# SiliconMind.net
KiCad netlist of a schematic drawn in EAGLE
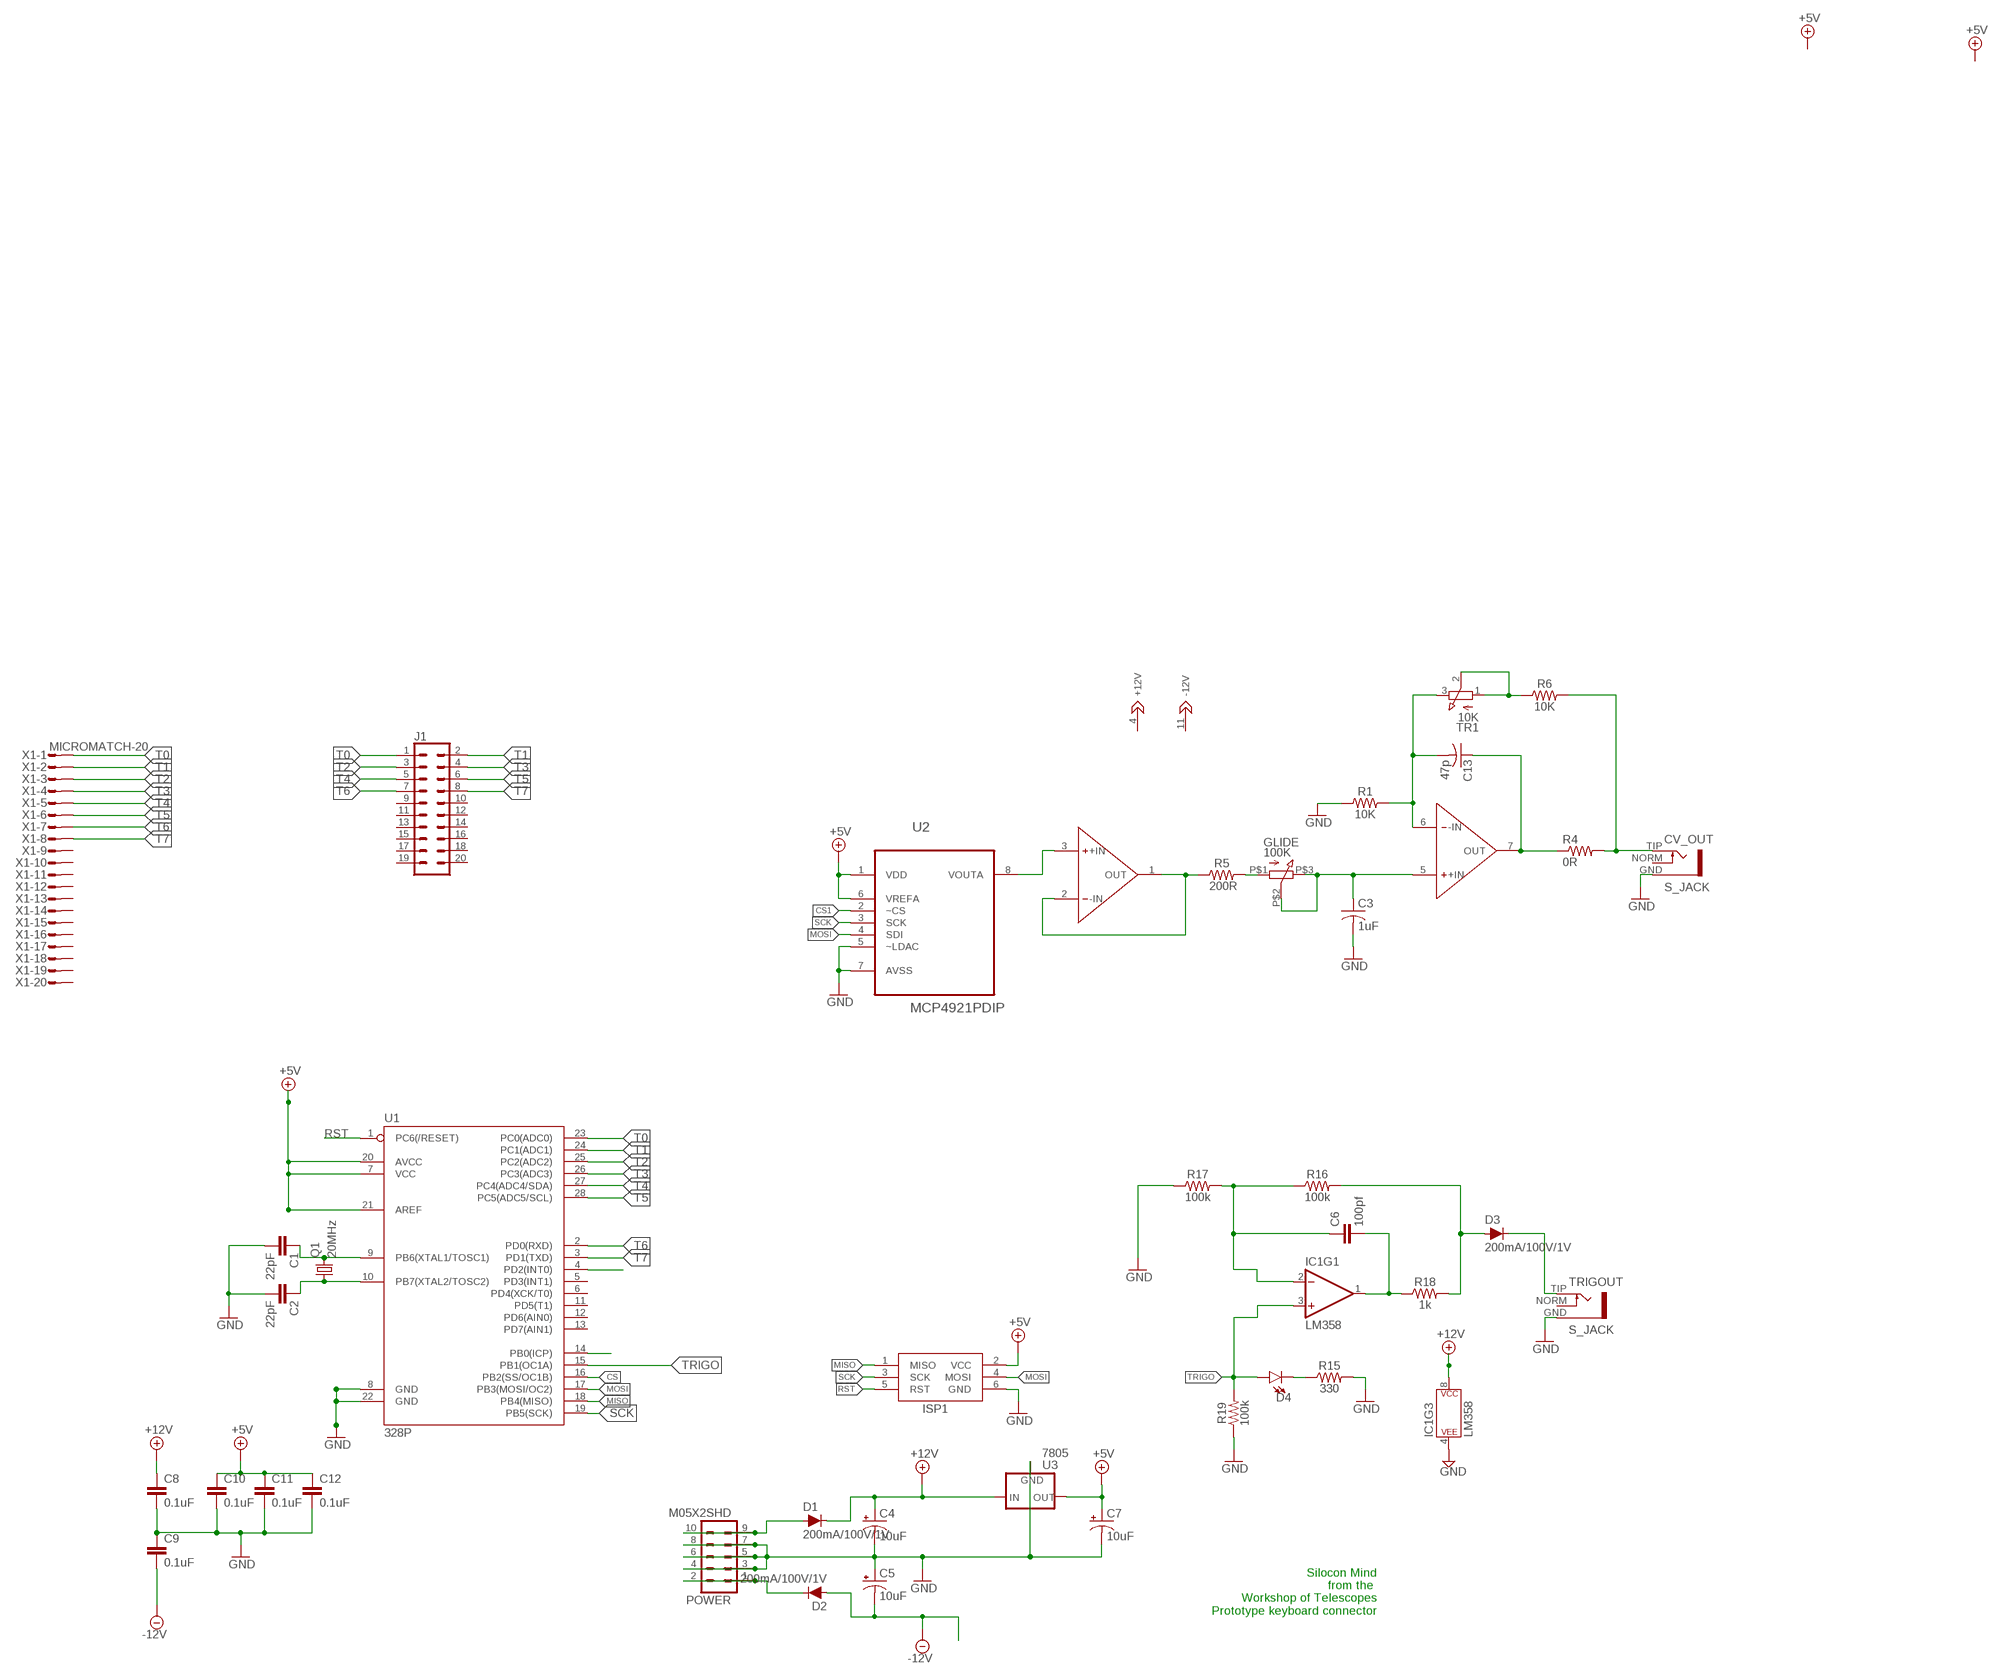
[diagram p0: schematic, sheet 1]

(export (version "E")
  (design (tool "Eeschema 10.0.6"))
  (components
    (comp (ref "C1")
      (value "22pF")
      (footprint "eagle-import:CAP-PTH-2.54")
      (libsource (lib "eagle-import") (part "22PF-PTH-2.54MM-200V-5%"))
    )
    (comp (ref "C2")
      (value "22pF")
      (footprint "eagle-import:CAP-PTH-2.54")
      (libsource (lib "eagle-import") (part "22PF-PTH-2.54MM-200V-5%"))
    )
    (comp (ref "C3")
      (value "1uF")
      (footprint "eagle-import:C0805K")
      (libsource (lib "eagle-import") (part "C-USC0805K"))
    )
    (comp (ref "C4")
      (value "10uF")
      (footprint "eagle-import:CPOL-RADIAL-2.5MM-5MM")
      (libsource (lib "eagle-import") (part "10UF-POLAR-RADIAL-2.5MM-25V-20%"))
    )
    (comp (ref "C5")
      (value "10uF")
      (footprint "eagle-import:CPOL-RADIAL-2.5MM-5MM")
      (libsource (lib "eagle-import") (part "10UF-POLAR-RADIAL-2.5MM-25V-20%"))
    )
    (comp (ref "C6")
      (value "100pf")
      (footprint "eagle-import:C075-032X103")
      (libsource (lib "eagle-import") (part "C-EU075-032X103"))
    )
    (comp (ref "C7")
      (value "10uF")
      (footprint "eagle-import:CPOL-RADIAL-2.5MM-5MM")
      (libsource (lib "eagle-import") (part "10UF-POLAR-RADIAL-2.5MM-25V-20%"))
    )
    (comp (ref "C8")
      (value "0.1uF")
      (footprint "eagle-import:CAP-PTH-SMALL-KIT")
      (libsource (lib "eagle-import") (part "0.1UF-KIT-EZ-50V-20%"))
    )
    (comp (ref "C9")
      (value "0.1uF")
      (footprint "eagle-import:CAP-PTH-SMALL-KIT")
      (libsource (lib "eagle-import") (part "0.1UF-KIT-EZ-50V-20%"))
    )
    (comp (ref "C10")
      (value "0.1uF")
      (footprint "eagle-import:CAP-PTH-SMALL-KIT")
      (libsource (lib "eagle-import") (part "0.1UF-KIT-EZ-50V-20%"))
    )
    (comp (ref "C11")
      (value "0.1uF")
      (footprint "eagle-import:CAP-PTH-SMALL-KIT")
      (libsource (lib "eagle-import") (part "0.1UF-KIT-EZ-50V-20%"))
    )
    (comp (ref "C12")
      (value "0.1uF")
      (footprint "eagle-import:CAP-PTH-SMALL-KIT")
      (libsource (lib "eagle-import") (part "0.1UF-KIT-EZ-50V-20%"))
    )
    (comp (ref "C13")
      (value "47p")
      (footprint "eagle-import:C0805K")
      (libsource (lib "eagle-import") (part "C-USC0805K"))
    )
    (comp (ref "CV_OUT")
      (value "S_JACK")
      (footprint "eagle-import:S_JACK")
      (libsource (lib "eagle-import") (part "S_JACK"))
    )
    (comp (ref "D1")
      (value "200mA/100V/1V")
      (footprint "eagle-import:DIODE-1N4148")
      (libsource (lib "eagle-import") (part "DIODE-1N4148"))
    )
    (comp (ref "D2")
      (value "200mA/100V/1V")
      (footprint "eagle-import:DIODE-1N4148")
      (libsource (lib "eagle-import") (part "DIODE-1N4148"))
    )
    (comp (ref "D3")
      (value "200mA/100V/1V")
      (footprint "eagle-import:DIODE-1N4148")
      (libsource (lib "eagle-import") (part "DIODE-1N4148"))
    )
    (comp (ref "D4")
      (value "LED3MM")
      (footprint "eagle-import:LED_3MM")
      (libsource (lib "eagle-import") (part "LED3MM"))
    )
    (comp (ref "GLIDE")
      (value "100K")
      (footprint "eagle-import:Q-POT")
      (libsource (lib "eagle-import") (part "Q-POT"))
    )
    (comp (ref "IC1")
      (value "LM358")
      (footprint "eagle-import:DIP08")
      (libsource (lib "eagle-import") (part "LM358"))
    )
    (comp (ref "ISP1")
      (value "AVRISP-6")
      (footprint "eagle-import:AVRISP")
      (libsource (lib "eagle-import") (part "AVRISP-6"))
    )
    (comp (ref "J1")
      (value "CONN_10X2")
      (footprint "eagle-import:2X10")
      (libsource (lib "eagle-import") (part "CONN_10X2"))
    )
    (comp (ref "POWER")
      (value "M05X2SHD")
      (footprint "eagle-import:2X5-SHROUDED")
      (libsource (lib "eagle-import") (part "M05X2SHD"))
    )
    (comp (ref "Q1")
      (value "20MHz")
      (footprint "eagle-import:HC49U70")
      (libsource (lib "eagle-import") (part "CRYSTALHC49U70"))
    )
    (comp (ref "R1")
      (value "10K")
      (footprint "eagle-import:AXIAL-0.3")
      (libsource (lib "eagle-import") (part "RESISTORAXIAL-0.3"))
    )
    (comp (ref "R4")
      (value "0R")
      (footprint "eagle-import:R0805")
      (libsource (lib "eagle-import") (part "R-US_R0805"))
    )
    (comp (ref "R5")
      (value "200R")
      (footprint "eagle-import:AXIAL-0.3")
      (libsource (lib "eagle-import") (part "RESISTORAXIAL-0.3"))
    )
    (comp (ref "R6")
      (value "10K")
      (footprint "eagle-import:AXIAL-0.3")
      (libsource (lib "eagle-import") (part "RESISTORAXIAL-0.3"))
    )
    (comp (ref "R15")
      (value "330")
      (footprint "eagle-import:AXIAL-0.3")
      (libsource (lib "eagle-import") (part "330OHM-HORIZ-1/10W-5%"))
    )
    (comp (ref "R16")
      (value "100k")
      (footprint "eagle-import:AXIAL-0.3")
      (libsource (lib "eagle-import") (part "100KOHM-HORIZ-1/4W-5%"))
    )
    (comp (ref "R17")
      (value "100k")
      (footprint "eagle-import:AXIAL-0.3")
      (libsource (lib "eagle-import") (part "100KOHM-HORIZ-1/4W-5%"))
    )
    (comp (ref "R18")
      (value "1k")
      (footprint "eagle-import:AXIAL-0.3")
      (libsource (lib "eagle-import") (part "1KOHM-HORIZ-1/4W-5%"))
    )
    (comp (ref "R19")
      (value "100k")
      (footprint "eagle-import:AXIAL-0.3")
      (libsource (lib "eagle-import") (part "100KOHM-HORIZ-1/4W-5%"))
    )
    (comp (ref "TR1")
      (value "10K")
      (footprint "eagle-import:TRIM_3269W")
      (libsource (lib "eagle-import") (part "TRIM_3269W"))
    )
    (comp (ref "TRIGOUT")
      (value "S_JACK")
      (footprint "eagle-import:S_JACK")
      (libsource (lib "eagle-import") (part "S_JACK"))
    )
    (comp (ref "U1")
      (value "328P")
      (footprint "eagle-import:DIP28")
      (libsource (lib "eagle-import") (part "ATMEGA328P_PDIP"))
    )
    (comp (ref "U2")
      (value "MCP4921PDIP")
      (footprint "eagle-import:DIP08")
      (libsource (lib "eagle-import") (part "MCP4921PDIP"))
    )
    (comp (ref "U3")
      (value "7805")
      (footprint "eagle-import:TO-220-ALT")
      (libsource (lib "eagle-import") (part "V_REG_78XX-TO-220"))
    )
    (comp (ref "U4")
      (value "QUAD_OPAMPDIP14")
      (footprint "eagle-import:DIP254P762X533-14")
      (libsource (lib "eagle-import") (part "QUAD_OPAMPDIP14"))
    )
    (comp (ref "X1")
      (value "MICROMATCH-20")
      (footprint "eagle-import:MICROMATCH-20")
      (fields (field (name "MF") "FARNELL") (field (name "MPN") "9-215464-0"))
      (libsource (lib "eagle-import") (part "MICROMATCH-20"))
    )
  )
  (nets
    (net (code "1") (name "+5V") (class "Default")
      (node (ref "C10") (pin "1") (pinfunction "1_1") (pintype "passive"))
      (node (ref "C11") (pin "1") (pinfunction "1_1") (pintype "passive"))
      (node (ref "C12") (pin "1") (pinfunction "1_1") (pintype "passive"))
      (node (ref "C7") (pin "1") (pinfunction "+_1") (pintype "passive"))
      (node (ref "ISP1") (pin "2") (pinfunction "VCC_2") (pintype "power_in"))
      (node (ref "U1") (pin "20") (pinfunction "AVCC_20") (pintype "bidirectional"))
      (node (ref "U1") (pin "21") (pinfunction "AREF_21") (pintype "bidirectional"))
      (node (ref "U1") (pin "7") (pinfunction "VCC_7") (pintype "bidirectional"))
      (node (ref "U2") (pin "1") (pinfunction "VDD_1") (pintype "power_in"))
      (node (ref "U2") (pin "6") (pinfunction "VREFA_6") (pintype "input"))
      (node (ref "U3") (pin "OUT") (pinfunction "OUT_OUT") (pintype "passive"))
    )
    (net (code "2") (name "+12V") (class "Default")
      (node (ref "C4") (pin "1") (pinfunction "+_1") (pintype "passive"))
      (node (ref "C8") (pin "1") (pinfunction "1_1") (pintype "passive"))
      (node (ref "D1") (pin "C") (pinfunction "C_C") (pintype "passive"))
      (node (ref "IC1") (pin "8") (pinfunction "P$V+_8") (pintype "bidirectional"))
      (node (ref "U3") (pin "IN") (pinfunction "IN_IN") (pintype "input"))
    )
    (net (code "3") (name "-12V") (class "Default")
      (node (ref "C5") (pin "2") (pinfunction "-_2") (pintype "passive"))
      (node (ref "C9") (pin "2") (pinfunction "2_2") (pintype "passive"))
      (node (ref "D2") (pin "A") (pinfunction "A_A") (pintype "passive"))
    )
    (net (code "4") (name "CS") (class "Default")
      (node (ref "U1") (pin "16") (pinfunction "PB2(SS/OC1B)_16") (pintype "bidirectional"))
    )
    (net (code "5") (name "CS1") (class "Default")
      (node (ref "U2") (pin "2") (pinfunction "~{CS}_2") (pintype "input"))
    )
    (net (code "6") (name "GND") (class "Default")
      (node (ref "C1") (pin "2") (pinfunction "2_2") (pintype "passive"))
      (node (ref "C10") (pin "2") (pinfunction "2_2") (pintype "passive"))
      (node (ref "C11") (pin "2") (pinfunction "2_2") (pintype "passive"))
      (node (ref "C12") (pin "2") (pinfunction "2_2") (pintype "passive"))
      (node (ref "C2") (pin "2") (pinfunction "2_2") (pintype "passive"))
      (node (ref "C3") (pin "2") (pinfunction "2_2") (pintype "passive"))
      (node (ref "C4") (pin "2") (pinfunction "-_2") (pintype "passive"))
      (node (ref "C5") (pin "1") (pinfunction "+_1") (pintype "passive"))
      (node (ref "C7") (pin "2") (pinfunction "-_2") (pintype "passive"))
      (node (ref "C8") (pin "2") (pinfunction "2_2") (pintype "passive"))
      (node (ref "C9") (pin "1") (pinfunction "1_1") (pintype "passive"))
      (node (ref "CV_OUT") (pin "GND") (pinfunction "GND_GND") (pintype "passive"))
      (node (ref "IC1") (pin "4") (pinfunction "P$V-_4") (pintype "bidirectional"))
      (node (ref "ISP1") (pin "6") (pinfunction "GND_6") (pintype "power_in"))
      (node (ref "POWER") (pin "3") (pinfunction "3_3") (pintype "passive"))
      (node (ref "POWER") (pin "4") (pinfunction "4_4") (pintype "passive"))
      (node (ref "POWER") (pin "5") (pinfunction "5_5") (pintype "passive"))
      (node (ref "POWER") (pin "6") (pinfunction "6_6") (pintype "passive"))
      (node (ref "POWER") (pin "7") (pinfunction "7_7") (pintype "passive"))
      (node (ref "POWER") (pin "8") (pinfunction "8_8") (pintype "passive"))
      (node (ref "R1") (pin "P$1") (pinfunction "1_P$1") (pintype "passive"))
      (node (ref "R15") (pin "P$2") (pinfunction "2_P$2") (pintype "passive"))
      (node (ref "R17") (pin "P$1") (pinfunction "1_P$1") (pintype "passive"))
      (node (ref "R19") (pin "P$1") (pinfunction "1_P$1") (pintype "passive"))
      (node (ref "TRIGOUT") (pin "GND") (pinfunction "GND_GND") (pintype "passive"))
      (node (ref "U1") (pin "22") (pinfunction "GND_22") (pintype "bidirectional"))
      (node (ref "U1") (pin "8") (pinfunction "GND_8") (pintype "bidirectional"))
      (node (ref "U2") (pin "5") (pinfunction "~{LDAC}_5") (pintype "input"))
      (node (ref "U2") (pin "7") (pinfunction "AVSS_7") (pintype "passive"))
      (node (ref "U3") (pin "GND") (pinfunction "GND_GND") (pintype "input"))
    )
    (net (code "7") (name "MISO") (class "Default")
      (node (ref "ISP1") (pin "1") (pinfunction "MISO_1") (pintype "input"))
      (node (ref "U1") (pin "18") (pinfunction "PB4(MISO)_18") (pintype "bidirectional"))
    )
    (net (code "8") (name "MOSI") (class "Default")
      (node (ref "ISP1") (pin "4") (pinfunction "MOSI_4") (pintype "output"))
      (node (ref "U1") (pin "17") (pinfunction "PB3(MOSI/OC2)_17") (pintype "bidirectional"))
      (node (ref "U2") (pin "4") (pinfunction "SDI_4") (pintype "input"))
    )
    (net (code "9") (name "Net-(D1-PadA)") (class "Default")
      (node (ref "D1") (pin "A") (pinfunction "A_A") (pintype "passive"))
      (node (ref "POWER") (pin "10") (pinfunction "10_10") (pintype "passive"))
      (node (ref "POWER") (pin "9") (pinfunction "9_9") (pintype "passive"))
    )
    (net (code "10") (name "Net-(D2-PadC)") (class "Default")
      (node (ref "D2") (pin "C") (pinfunction "C_C") (pintype "passive"))
      (node (ref "POWER") (pin "1") (pinfunction "1_1") (pintype "passive"))
      (node (ref "POWER") (pin "2") (pinfunction "2_2") (pintype "passive"))
    )
    (net (code "11") (name "Net-(D3-PadC)") (class "Default")
      (node (ref "D3") (pin "C") (pinfunction "C_C") (pintype "passive"))
      (node (ref "TRIGOUT") (pin "TIP") (pinfunction "TIP_TIP") (pintype "passive"))
    )
    (net (code "12") (name "Net-(D4-C)") (class "Default")
      (node (ref "D4") (pin "K") (pinfunction "C_K") (pintype "passive"))
      (node (ref "R15") (pin "P$1") (pinfunction "1_P$1") (pintype "passive"))
    )
    (net (code "13") (name "Net-(GLIDE-1)") (class "Default")
      (node (ref "GLIDE") (pin "P$1") (pinfunction "1_P$1") (pintype "passive"))
      (node (ref "R5") (pin "P$2") (pinfunction "2_P$2") (pintype "passive"))
    )
    (net (code "14") (name "Net-(GLIDE-2)") (class "Default")
      (node (ref "C3") (pin "1") (pinfunction "1_1") (pintype "passive"))
      (node (ref "GLIDE") (pin "P$2") (pinfunction "2_P$2") (pintype "passive"))
      (node (ref "GLIDE") (pin "P$3") (pinfunction "3_P$3") (pintype "passive"))
      (node (ref "U4") (pin "5") (pinfunction "+IN_5") (pintype "bidirectional"))
    )
    (net (code "15") (name "Net-(IC1A--IN)") (class "Default")
      (node (ref "C6") (pin "1") (pinfunction "1_1") (pintype "passive"))
      (node (ref "IC1") (pin "2") (pinfunction "-IN_2") (pintype "input"))
      (node (ref "R16") (pin "P$1") (pinfunction "1_P$1") (pintype "passive"))
      (node (ref "R17") (pin "P$2") (pinfunction "2_P$2") (pintype "passive"))
    )
    (net (code "16") (name "Net-(IC1A-OUT)") (class "Default")
      (node (ref "C6") (pin "2") (pinfunction "2_2") (pintype "passive"))
      (node (ref "IC1") (pin "1") (pinfunction "OUT_1") (pintype "output"))
      (node (ref "R18") (pin "P$1") (pinfunction "1_P$1") (pintype "passive"))
    )
    (net (code "17") (name "Net-(R1-2)") (class "Default")
      (node (ref "C13") (pin "2") (pinfunction "2_2") (pintype "passive"))
      (node (ref "R1") (pin "P$2") (pinfunction "2_P$2") (pintype "passive"))
      (node (ref "TR1") (pin "3") (pinfunction "3_3") (pintype "passive"))
      (node (ref "U4") (pin "6") (pinfunction "-IN_6") (pintype "bidirectional"))
    )
    (net (code "18") (name "Net-(R5-1)") (class "Default")
      (node (ref "R5") (pin "P$1") (pinfunction "1_P$1") (pintype "passive"))
      (node (ref "U4") (pin "1") (pinfunction "OUT_1") (pintype "bidirectional"))
      (node (ref "U4") (pin "2") (pinfunction "-IN_2") (pintype "bidirectional"))
    )
    (net (code "19") (name "Net-(R6-1)") (class "Default")
      (node (ref "R6") (pin "P$1") (pinfunction "1_P$1") (pintype "passive"))
      (node (ref "TR1") (pin "1") (pinfunction "1_1") (pintype "passive"))
      (node (ref "TR1") (pin "2") (pinfunction "2_2") (pintype "passive"))
    )
    (net (code "20") (name "Net-(R6-2)") (class "Default")
      (node (ref "CV_OUT") (pin "TIP") (pinfunction "TIP_TIP") (pintype "passive"))
      (node (ref "R4") (pin "2") (pinfunction "2_2") (pintype "passive"))
      (node (ref "R6") (pin "P$2") (pinfunction "2_P$2") (pintype "passive"))
    )
    (net (code "21") (name "Net-(R16-2)") (class "Default")
      (node (ref "D3") (pin "A") (pinfunction "A_A") (pintype "passive"))
      (node (ref "R16") (pin "P$2") (pinfunction "2_P$2") (pintype "passive"))
      (node (ref "R18") (pin "P$2") (pinfunction "2_P$2") (pintype "passive"))
    )
    (net (code "22") (name "Net-(U1-PB6(XTAL1{slash}TOSC1))") (class "Default")
      (node (ref "C1") (pin "1") (pinfunction "1_1") (pintype "passive"))
      (node (ref "Q1") (pin "2") (pinfunction "2_2") (pintype "passive"))
      (node (ref "U1") (pin "9") (pinfunction "PB6(XTAL1/TOSC1)_9") (pintype "bidirectional"))
    )
    (net (code "23") (name "Net-(U1-PB7(XTAL2{slash}TOSC2))") (class "Default")
      (node (ref "C2") (pin "1") (pinfunction "1_1") (pintype "passive"))
      (node (ref "Q1") (pin "1") (pinfunction "1_1") (pintype "passive"))
      (node (ref "U1") (pin "10") (pinfunction "PB7(XTAL2/TOSC2)_10") (pintype "bidirectional"))
    )
    (net (code "24") (name "Net-(U2-VOUTA)") (class "Default")
      (node (ref "U2") (pin "8") (pinfunction "VOUTA_8") (pintype "output"))
      (node (ref "U4") (pin "3") (pinfunction "+IN_3") (pintype "bidirectional"))
    )
    (net (code "25") (name "Net-(U4B-OUT)") (class "Default")
      (node (ref "C13") (pin "1") (pinfunction "1_1") (pintype "passive"))
      (node (ref "R4") (pin "1") (pinfunction "1_1") (pintype "passive"))
      (node (ref "U4") (pin "7") (pinfunction "OUT_7") (pintype "bidirectional"))
    )
    (net (code "26") (name "RST") (class "Default")
      (node (ref "ISP1") (pin "5") (pinfunction "RST_5") (pintype "output"))
      (node (ref "U1") (pin "1") (pinfunction "PC6(/RESET)_1") (pintype "bidirectional"))
    )
    (net (code "27") (name "SCK") (class "Default")
      (node (ref "ISP1") (pin "3") (pinfunction "SCK_3") (pintype "output"))
      (node (ref "U1") (pin "19") (pinfunction "PB5(SCK)_19") (pintype "bidirectional"))
      (node (ref "U2") (pin "3") (pinfunction "SCK_3") (pintype "input"))
    )
    (net (code "28") (name "T0") (class "Default")
      (node (ref "J1") (pin "1") (pinfunction "1_1") (pintype "passive"))
      (node (ref "U1") (pin "23") (pinfunction "PC0(ADC0)_23") (pintype "bidirectional"))
      (node (ref "X1") (pin "1") (pinfunction "S_1") (pintype "passive"))
    )
    (net (code "29") (name "T1") (class "Default")
      (node (ref "J1") (pin "2") (pinfunction "2_2") (pintype "passive"))
      (node (ref "U1") (pin "24") (pinfunction "PC1(ADC1)_24") (pintype "bidirectional"))
      (node (ref "X1") (pin "2") (pinfunction "S_2") (pintype "passive"))
    )
    (net (code "30") (name "T2") (class "Default")
      (node (ref "J1") (pin "3") (pinfunction "3_3") (pintype "passive"))
      (node (ref "U1") (pin "25") (pinfunction "PC2(ADC2)_25") (pintype "bidirectional"))
      (node (ref "X1") (pin "3") (pinfunction "S_3") (pintype "passive"))
    )
    (net (code "31") (name "T3") (class "Default")
      (node (ref "J1") (pin "4") (pinfunction "4_4") (pintype "passive"))
      (node (ref "U1") (pin "26") (pinfunction "PC3(ADC3)_26") (pintype "bidirectional"))
      (node (ref "X1") (pin "4") (pinfunction "S_4") (pintype "passive"))
    )
    (net (code "32") (name "T4") (class "Default")
      (node (ref "J1") (pin "5") (pinfunction "5_5") (pintype "passive"))
      (node (ref "U1") (pin "27") (pinfunction "PC4(ADC4/SDA)_27") (pintype "bidirectional"))
      (node (ref "X1") (pin "5") (pinfunction "S_5") (pintype "passive"))
    )
    (net (code "33") (name "T5") (class "Default")
      (node (ref "J1") (pin "6") (pinfunction "6_6") (pintype "passive"))
      (node (ref "U1") (pin "28") (pinfunction "PC5(ADC5/SCL)_28") (pintype "bidirectional"))
      (node (ref "X1") (pin "6") (pinfunction "S_6") (pintype "passive"))
    )
    (net (code "34") (name "T6") (class "Default")
      (node (ref "J1") (pin "7") (pinfunction "7_7") (pintype "passive"))
      (node (ref "U1") (pin "2") (pinfunction "PD0(RXD)_2") (pintype "bidirectional"))
      (node (ref "X1") (pin "7") (pinfunction "S_7") (pintype "passive"))
    )
    (net (code "35") (name "T7") (class "Default")
      (node (ref "J1") (pin "8") (pinfunction "8_8") (pintype "passive"))
      (node (ref "U1") (pin "3") (pinfunction "PD1(TXD)_3") (pintype "bidirectional"))
      (node (ref "X1") (pin "8") (pinfunction "S_8") (pintype "passive"))
    )
    (net (code "36") (name "TRIGO") (class "Default")
      (node (ref "D4") (pin "A") (pinfunction "A_A") (pintype "passive"))
      (node (ref "IC1") (pin "3") (pinfunction "+IN_3") (pintype "input"))
      (node (ref "R19") (pin "P$2") (pinfunction "2_P$2") (pintype "passive"))
      (node (ref "U1") (pin "14") (pinfunction "PB0(ICP)_14") (pintype "bidirectional"))
    )
    (net (code "37") (name "unconnected-(CV_OUT-PadNORM)") (class "Default")
      (node (ref "CV_OUT") (pin "NORM") (pinfunction "NORM_NORM") (pintype "passive"))
    )
    (net (code "38") (name "unconnected-(J1-Pad9)") (class "Default")
      (node (ref "J1") (pin "9") (pinfunction "9_9") (pintype "passive"))
    )
    (net (code "39") (name "unconnected-(J1-Pad10)") (class "Default")
      (node (ref "J1") (pin "10") (pinfunction "10_10") (pintype "passive"))
    )
    (net (code "40") (name "unconnected-(J1-Pad11)") (class "Default")
      (node (ref "J1") (pin "11") (pinfunction "11_11") (pintype "passive"))
    )
    (net (code "41") (name "unconnected-(J1-Pad12)") (class "Default")
      (node (ref "J1") (pin "12") (pinfunction "12_12") (pintype "passive"))
    )
    (net (code "42") (name "unconnected-(J1-Pad13)") (class "Default")
      (node (ref "J1") (pin "13") (pinfunction "13_13") (pintype "passive"))
    )
    (net (code "43") (name "unconnected-(J1-Pad14)") (class "Default")
      (node (ref "J1") (pin "14") (pinfunction "14_14") (pintype "passive"))
    )
    (net (code "44") (name "unconnected-(J1-Pad15)") (class "Default")
      (node (ref "J1") (pin "15") (pinfunction "15_15") (pintype "passive"))
    )
    (net (code "45") (name "unconnected-(J1-Pad16)") (class "Default")
      (node (ref "J1") (pin "16") (pinfunction "16_16") (pintype "passive"))
    )
    (net (code "46") (name "unconnected-(J1-Pad17)") (class "Default")
      (node (ref "J1") (pin "17") (pinfunction "17_17") (pintype "passive"))
    )
    (net (code "47") (name "unconnected-(J1-Pad18)") (class "Default")
      (node (ref "J1") (pin "18") (pinfunction "18_18") (pintype "passive"))
    )
    (net (code "48") (name "unconnected-(J1-Pad19)") (class "Default")
      (node (ref "J1") (pin "19") (pinfunction "19_19") (pintype "passive"))
    )
    (net (code "49") (name "unconnected-(J1-Pad20)") (class "Default")
      (node (ref "J1") (pin "20") (pinfunction "20_20") (pintype "passive"))
    )
    (net (code "50") (name "unconnected-(TRIGOUT-PadNORM)") (class "Default")
      (node (ref "TRIGOUT") (pin "NORM") (pinfunction "NORM_NORM") (pintype "passive"))
    )
    (net (code "51") (name "unconnected-(U1-PB1(OC1A)-Pad15)") (class "Default")
      (node (ref "U1") (pin "15") (pinfunction "PB1(OC1A)_15") (pintype "bidirectional"))
    )
    (net (code "52") (name "unconnected-(U1-PD2(INT0)-Pad4)") (class "Default")
      (node (ref "U1") (pin "4") (pinfunction "PD2(INT0)_4") (pintype "bidirectional"))
    )
    (net (code "53") (name "unconnected-(U1-PD3(INT1)-Pad5)") (class "Default")
      (node (ref "U1") (pin "5") (pinfunction "PD3(INT1)_5") (pintype "bidirectional"))
    )
    (net (code "54") (name "unconnected-(U1-PD4(XCK{slash}T0)-Pad6)") (class "Default")
      (node (ref "U1") (pin "6") (pinfunction "PD4(XCK/T0)_6") (pintype "bidirectional"))
    )
    (net (code "55") (name "unconnected-(U1-PD5(T1)-Pad11)") (class "Default")
      (node (ref "U1") (pin "11") (pinfunction "PD5(T1)_11") (pintype "bidirectional"))
    )
    (net (code "56") (name "unconnected-(U1-PD6(AIN0)-Pad12)") (class "Default")
      (node (ref "U1") (pin "12") (pinfunction "PD6(AIN0)_12") (pintype "bidirectional"))
    )
    (net (code "57") (name "unconnected-(U1-PD7(AIN1)-Pad13)") (class "Default")
      (node (ref "U1") (pin "13") (pinfunction "PD7(AIN1)_13") (pintype "bidirectional"))
    )
    (net (code "58") (name "unconnected-(U4E-+12V-Pad4)") (class "Default")
      (node (ref "U4") (pin "4") (pinfunction "+12V_4") (pintype "bidirectional"))
    )
    (net (code "59") (name "unconnected-(U4F--12V-Pad11)") (class "Default")
      (node (ref "U4") (pin "11") (pinfunction "-12V_11") (pintype "bidirectional"))
    )
    (net (code "60") (name "unconnected-(X1B-S-Pad10)") (class "Default")
      (node (ref "X1") (pin "10") (pinfunction "S_10") (pintype "passive"))
    )
    (net (code "61") (name "unconnected-(X1C-S-Pad11)") (class "Default")
      (node (ref "X1") (pin "11") (pinfunction "S_11") (pintype "passive"))
    )
    (net (code "62") (name "unconnected-(X1D-S-Pad12)") (class "Default")
      (node (ref "X1") (pin "12") (pinfunction "S_12") (pintype "passive"))
    )
    (net (code "63") (name "unconnected-(X1E-S-Pad13)") (class "Default")
      (node (ref "X1") (pin "13") (pinfunction "S_13") (pintype "passive"))
    )
    (net (code "64") (name "unconnected-(X1F-S-Pad14)") (class "Default")
      (node (ref "X1") (pin "14") (pinfunction "S_14") (pintype "passive"))
    )
    (net (code "65") (name "unconnected-(X1G-S-Pad15)") (class "Default")
      (node (ref "X1") (pin "15") (pinfunction "S_15") (pintype "passive"))
    )
    (net (code "66") (name "unconnected-(X1H-S-Pad16)") (class "Default")
      (node (ref "X1") (pin "16") (pinfunction "S_16") (pintype "passive"))
    )
    (net (code "67") (name "unconnected-(X1I-S-Pad17)") (class "Default")
      (node (ref "X1") (pin "17") (pinfunction "S_17") (pintype "passive"))
    )
    (net (code "68") (name "unconnected-(X1J-S-Pad18)") (class "Default")
      (node (ref "X1") (pin "18") (pinfunction "S_18") (pintype "passive"))
    )
    (net (code "69") (name "unconnected-(X1K-S-Pad19)") (class "Default")
      (node (ref "X1") (pin "19") (pinfunction "S_19") (pintype "passive"))
    )
    (net (code "70") (name "unconnected-(X1M-S-Pad20)") (class "Default")
      (node (ref "X1") (pin "20") (pinfunction "S_20") (pintype "passive"))
    )
    (net (code "71") (name "unconnected-(X1T-S-Pad9)") (class "Default")
      (node (ref "X1") (pin "9") (pinfunction "S_9") (pintype "passive"))
    )
  )
)
